# StepStick_Driver.net
KiCad netlist of a schematic drawn in Altium Designer
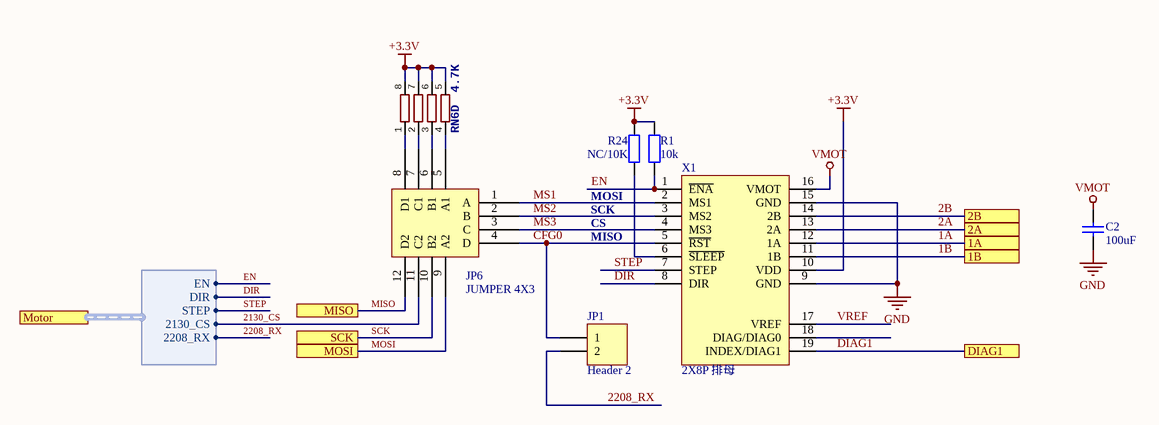
[diagram p0: StepStick_Driver.SchDoc]

(export (version "E")
  (design (tool "Eeschema 10.0.6"))
  (components
    (comp (ref "C2") (value "100uF") (footprint "ELCO Case D") (libsource (lib "接插件库") (part "Capacitor")))
    (comp (ref "JP1")
      (value "Header 2")
      (footprint "HDR1X2")
      (description "Header, 2-Pin")
      (fields (field (name "PUBLISHER") "Altium Limited"))
      (libsource (lib "Miscellaneous Connectors") (part "Header 2"))
    )
    (comp (ref "JP6")
      (value "JUMPER 4X3")
      (footprint "HEADER 3x4")
      (libsource (lib "接插件库") (part "JUMPER 4X3"))
    )
    (comp (ref "R1")
      (value "10k")
      (footprint "RES0603")
      (description "RO RES 1k0 1% 0,1W  0603")
      (libsource (lib "Ultimaker2") (part "Resistor_2"))
    )
    (comp (ref "R24")
      (value "NC/10K")
      (footprint "RES0603")
      (description "RO RES 1k0 1% 0,1W  0603")
      (libsource (lib "Ultimaker2") (part "Resistor_2"))
    )
    (comp (ref "RN6")
      (value "4.7K")
      (footprint "RESISTOR-DIL_CAY16")
      (libsource (lib "接插件库") (part "RESISTOR-DIL_4R-NCAY16"))
    )
    (comp (ref "X1")
      (value "2X8P 排母")
      (footprint "TMC_breakout")
      (libsource (lib "接插件库") (part "TMC_BREAKOUT"))
    )
  )
  (nets
    (net (code "2") (name "+3.3V") (class "Default")
      (node (ref "R1") (pin "2") (pinfunction "2_2") (pintype "passive"))
      (node (ref "R24") (pin "2") (pinfunction "2_2") (pintype "passive"))
      (node (ref "RN6") (pin "5") (pinfunction "2_5") (pintype "passive"))
      (node (ref "RN6") (pin "6") (pinfunction "2_6") (pintype "passive"))
      (node (ref "RN6") (pin "7") (pinfunction "2_7") (pintype "passive"))
      (node (ref "RN6") (pin "8") (pinfunction "2_8") (pintype "passive"))
      (node (ref "X1") (pin "10") (pinfunction "VDD_10") (pintype "passive"))
    )
    (net (code "3") (name "/1A") (class "Default")
      (node (ref "X1") (pin "12") (pinfunction "1A_12") (pintype "passive"))
    )
    (net (code "4") (name "/1B") (class "Default")
      (node (ref "X1") (pin "11") (pinfunction "1B_11") (pintype "passive"))
    )
    (net (code "5") (name "/2A") (class "Default")
      (node (ref "X1") (pin "13") (pinfunction "2A_13") (pintype "passive"))
    )
    (net (code "6") (name "/2B") (class "Default")
      (node (ref "X1") (pin "14") (pinfunction "2B_14") (pintype "passive"))
    )
    (net (code "7") (name "/2130_CS") (class "Default")
      (node (ref "JP6") (pin "11") (pinfunction "C2_11") (pintype "passive"))
    )
    (net (code "8") (name "/2208_RX") (class "Default")
      (node (ref "JP1") (pin "2") (pinfunction "2_2") (pintype "passive"))
    )
    (net (code "9") (name "/CFG0") (class "Default")
      (node (ref "JP1") (pin "1") (pinfunction "1_1") (pintype "passive"))
      (node (ref "JP6") (pin "4") (pinfunction "D_4") (pintype "passive"))
      (node (ref "X1") (pin "5") (pinfunction "~{RST}_5") (pintype "passive"))
    )
    (net (code "10") (name "/DIAG1") (class "Default")
      (node (ref "X1") (pin "19") (pinfunction "INDEX/DIAG1_19") (pintype "passive"))
    )
    (net (code "11") (name "/DIR") (class "Default")
      (node (ref "X1") (pin "8") (pinfunction "DIR_8") (pintype "passive"))
    )
    (net (code "12") (name "/EN") (class "Default")
      (node (ref "R1") (pin "1") (pinfunction "1_1") (pintype "passive"))
      (node (ref "X1") (pin "1") (pinfunction "~{ENA}_1") (pintype "passive"))
    )
    (net (code "13") (name "/MISO") (class "Default")
      (node (ref "JP6") (pin "12") (pinfunction "D2_12") (pintype "passive"))
    )
    (net (code "14") (name "/MOSI") (class "Default")
      (node (ref "JP6") (pin "9") (pinfunction "A2_9") (pintype "passive"))
    )
    (net (code "15") (name "/MS1") (class "Default")
      (node (ref "JP6") (pin "1") (pinfunction "A_1") (pintype "passive"))
      (node (ref "X1") (pin "2") (pinfunction "MS1_2") (pintype "passive"))
    )
    (net (code "16") (name "/MS2") (class "Default")
      (node (ref "JP6") (pin "2") (pinfunction "B_2") (pintype "passive"))
      (node (ref "X1") (pin "3") (pinfunction "MS2_3") (pintype "passive"))
    )
    (net (code "17") (name "/MS3") (class "Default")
      (node (ref "JP6") (pin "3") (pinfunction "C_3") (pintype "passive"))
      (node (ref "X1") (pin "4") (pinfunction "MS3_4") (pintype "passive"))
    )
    (net (code "18") (name "/SCK") (class "Default")
      (node (ref "JP6") (pin "10") (pinfunction "B2_10") (pintype "passive"))
    )
    (net (code "19") (name "/STEP") (class "Default")
      (node (ref "X1") (pin "7") (pinfunction "STEP_7") (pintype "passive"))
    )
    (net (code "20") (name "/VREF") (class "Default")
      (node (ref "X1") (pin "17") (pinfunction "VREF_17") (pintype "passive"))
    )
    (net (code "22") (name "GND") (class "Default")
      (node (ref "C2") (pin "2") (pinfunction "2_2") (pintype "passive"))
      (node (ref "X1") (pin "15") (pinfunction "GND_15") (pintype "passive"))
      (node (ref "X1") (pin "9") (pinfunction "GND_9") (pintype "passive"))
    )
    (net (code "23") (name "Net-(JP6-A1)") (class "Default")
      (node (ref "JP6") (pin "5") (pinfunction "A1_5") (pintype "passive"))
      (node (ref "RN6") (pin "4") (pinfunction "1_4") (pintype "passive"))
    )
    (net (code "24") (name "Net-(JP6-B1)") (class "Default")
      (node (ref "JP6") (pin "6") (pinfunction "B1_6") (pintype "passive"))
      (node (ref "RN6") (pin "3") (pinfunction "1_3") (pintype "passive"))
    )
    (net (code "25") (name "Net-(JP6-C1)") (class "Default")
      (node (ref "JP6") (pin "7") (pinfunction "C1_7") (pintype "passive"))
      (node (ref "RN6") (pin "2") (pinfunction "1_2") (pintype "passive"))
    )
    (net (code "26") (name "Net-(JP6-D1)") (class "Default")
      (node (ref "JP6") (pin "8") (pinfunction "D1_8") (pintype "passive"))
      (node (ref "RN6") (pin "1") (pinfunction "1_1") (pintype "passive"))
    )
    (net (code "27") (name "Net-(X1-~{SLEEP})") (class "Default")
      (node (ref "R24") (pin "1") (pinfunction "1_1") (pintype "passive"))
      (node (ref "X1") (pin "6") (pinfunction "~{SLEEP}_6") (pintype "passive"))
    )
    (net (code "28") (name "VMOT") (class "Default")
      (node (ref "C2") (pin "1") (pinfunction "1_1") (pintype "passive"))
      (node (ref "X1") (pin "16") (pinfunction "VMOT_16") (pintype "passive"))
    )
    (net (code "29") (name "unconnected-(X1-DIAG{slash}DIAG0-Pad18)") (class "Default")
      (node (ref "X1") (pin "18") (pinfunction "DIAG/DIAG0_18") (pintype "passive"))
    )
  )
)
